# Breadboard_ProMini_v3.net
KiCad netlist of a schematic drawn in EAGLE
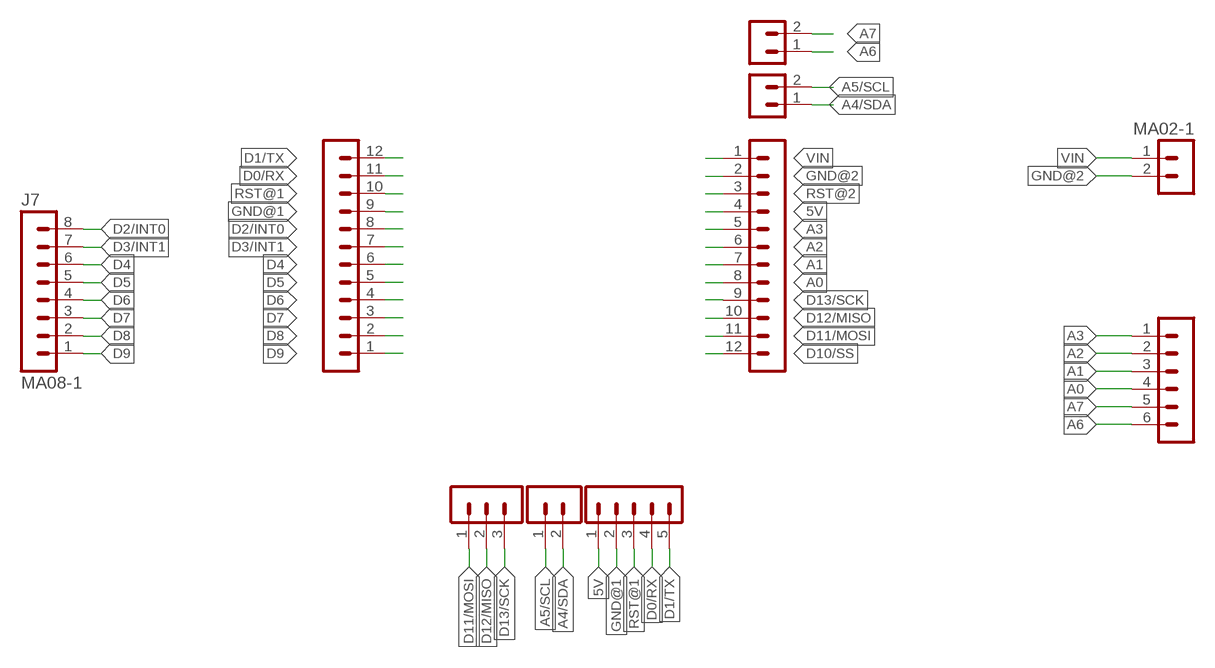
[diagram p0: schematic, sheet 1]

(export (version "E")
  (design (tool "Eeschema 10.0.6"))
  (components
    (comp (ref "J1")
      (value "MA05-1")
      (footprint "eagle-import:MA05-1")
      (libsource (lib "eagle-import") (part "MA05-1"))
    )
    (comp (ref "J3")
      (value "MA03-1")
      (footprint "eagle-import:MA03-1")
      (libsource (lib "eagle-import") (part "MA03-1"))
    )
    (comp (ref "J4")
      (value "MA12-1")
      (footprint "eagle-import:MA12-1")
      (libsource (lib "eagle-import") (part "MA12-1"))
    )
    (comp (ref "J5")
      (value "MA02-1")
      (footprint "eagle-import:MA02-1")
      (libsource (lib "eagle-import") (part "MA02-1"))
    )
    (comp (ref "J6")
      (value "MA02-1")
      (footprint "eagle-import:MA02-1")
      (libsource (lib "eagle-import") (part "00_marph_connectors_IDC_MA02-1"))
    )
    (comp (ref "J7")
      (value "MA08-1")
      (footprint "eagle-import:MA08-1")
      (libsource (lib "eagle-import") (part "MA08-1"))
    )
    (comp (ref "J8")
      (value "MA12-1")
      (footprint "eagle-import:MA12-1")
      (libsource (lib "eagle-import") (part "MA12-1"))
    )
    (comp (ref "J9")
      (value "MA02-1")
      (footprint "eagle-import:MA02-1")
      (libsource (lib "eagle-import") (part "00_marph_connectors_IDC_MA02-1"))
    )
    (comp (ref "J10")
      (value "MA02-1")
      (footprint "eagle-import:MA02-1")
      (libsource (lib "eagle-import") (part "MA02-1"))
    )
    (comp (ref "J11")
      (value "MA06-1")
      (footprint "eagle-import:MA06-1")
      (libsource (lib "eagle-import") (part "MA06-1"))
    )
  )
  (nets
    (net (code "1") (name "5V") (class "Default")
      (node (ref "J1") (pin "1") (pinfunction "1_1") (pintype "passive"))
      (node (ref "J8") (pin "4") (pinfunction "4_4") (pintype "passive"))
    )
    (net (code "2") (name "A0") (class "Default")
      (node (ref "J11") (pin "4") (pinfunction "4_4") (pintype "passive"))
      (node (ref "J8") (pin "8") (pinfunction "8_8") (pintype "passive"))
    )
    (net (code "3") (name "A1") (class "Default")
      (node (ref "J11") (pin "3") (pinfunction "3_3") (pintype "passive"))
      (node (ref "J8") (pin "7") (pinfunction "7_7") (pintype "passive"))
    )
    (net (code "4") (name "A2") (class "Default")
      (node (ref "J11") (pin "2") (pinfunction "2_2") (pintype "passive"))
      (node (ref "J8") (pin "6") (pinfunction "6_6") (pintype "passive"))
    )
    (net (code "5") (name "A3") (class "Default")
      (node (ref "J11") (pin "1") (pinfunction "1_1") (pintype "passive"))
      (node (ref "J8") (pin "5") (pinfunction "5_5") (pintype "passive"))
    )
    (net (code "6") (name "A4{slash}SDA") (class "Default")
      (node (ref "J10") (pin "1") (pinfunction "1_1") (pintype "passive"))
      (node (ref "J6") (pin "2") (pinfunction "2_2") (pintype "passive"))
    )
    (net (code "7") (name "A5{slash}SCL") (class "Default")
      (node (ref "J10") (pin "2") (pinfunction "2_2") (pintype "passive"))
      (node (ref "J6") (pin "1") (pinfunction "1_1") (pintype "passive"))
    )
    (net (code "8") (name "A6") (class "Default")
      (node (ref "J11") (pin "6") (pinfunction "6_6") (pintype "passive"))
      (node (ref "J5") (pin "1") (pinfunction "1_1") (pintype "passive"))
    )
    (net (code "9") (name "A7") (class "Default")
      (node (ref "J11") (pin "5") (pinfunction "5_5") (pintype "passive"))
      (node (ref "J5") (pin "2") (pinfunction "2_2") (pintype "passive"))
    )
    (net (code "10") (name "D0{slash}RX") (class "Default")
      (node (ref "J1") (pin "4") (pinfunction "4_4") (pintype "passive"))
      (node (ref "J4") (pin "11") (pinfunction "11_11") (pintype "passive"))
    )
    (net (code "11") (name "D1{slash}TX") (class "Default")
      (node (ref "J1") (pin "5") (pinfunction "5_5") (pintype "passive"))
      (node (ref "J4") (pin "12") (pinfunction "12_12") (pintype "passive"))
    )
    (net (code "12") (name "D2{slash}INT0") (class "Default")
      (node (ref "J4") (pin "8") (pinfunction "8_8") (pintype "passive"))
      (node (ref "J7") (pin "8") (pinfunction "8_8") (pintype "passive"))
    )
    (net (code "13") (name "D3{slash}INT1") (class "Default")
      (node (ref "J4") (pin "7") (pinfunction "7_7") (pintype "passive"))
      (node (ref "J7") (pin "7") (pinfunction "7_7") (pintype "passive"))
    )
    (net (code "14") (name "D4") (class "Default")
      (node (ref "J4") (pin "6") (pinfunction "6_6") (pintype "passive"))
      (node (ref "J7") (pin "6") (pinfunction "6_6") (pintype "passive"))
    )
    (net (code "15") (name "D5") (class "Default")
      (node (ref "J4") (pin "5") (pinfunction "5_5") (pintype "passive"))
      (node (ref "J7") (pin "5") (pinfunction "5_5") (pintype "passive"))
    )
    (net (code "16") (name "D6") (class "Default")
      (node (ref "J4") (pin "4") (pinfunction "4_4") (pintype "passive"))
      (node (ref "J7") (pin "4") (pinfunction "4_4") (pintype "passive"))
    )
    (net (code "17") (name "D7") (class "Default")
      (node (ref "J4") (pin "3") (pinfunction "3_3") (pintype "passive"))
      (node (ref "J7") (pin "3") (pinfunction "3_3") (pintype "passive"))
    )
    (net (code "18") (name "D8") (class "Default")
      (node (ref "J4") (pin "2") (pinfunction "2_2") (pintype "passive"))
      (node (ref "J7") (pin "2") (pinfunction "2_2") (pintype "passive"))
    )
    (net (code "19") (name "D9") (class "Default")
      (node (ref "J4") (pin "1") (pinfunction "1_1") (pintype "passive"))
      (node (ref "J7") (pin "1") (pinfunction "1_1") (pintype "passive"))
    )
    (net (code "20") (name "D10{slash}SS") (class "Default")
      (node (ref "J8") (pin "12") (pinfunction "12_12") (pintype "passive"))
    )
    (net (code "21") (name "D11{slash}MOSI") (class "Default")
      (node (ref "J3") (pin "1") (pinfunction "1_1") (pintype "passive"))
      (node (ref "J8") (pin "11") (pinfunction "11_11") (pintype "passive"))
    )
    (net (code "22") (name "D12{slash}MISO") (class "Default")
      (node (ref "J3") (pin "2") (pinfunction "2_2") (pintype "passive"))
      (node (ref "J8") (pin "10") (pinfunction "10_10") (pintype "passive"))
    )
    (net (code "23") (name "D13{slash}SCK") (class "Default")
      (node (ref "J3") (pin "3") (pinfunction "3_3") (pintype "passive"))
      (node (ref "J8") (pin "9") (pinfunction "9_9") (pintype "passive"))
    )
    (net (code "24") (name "GND@1") (class "Default")
      (node (ref "J1") (pin "2") (pinfunction "2_2") (pintype "passive"))
      (node (ref "J4") (pin "9") (pinfunction "9_9") (pintype "passive"))
    )
    (net (code "25") (name "GND@2") (class "Default")
      (node (ref "J8") (pin "2") (pinfunction "2_2") (pintype "passive"))
      (node (ref "J9") (pin "2") (pinfunction "2_2") (pintype "passive"))
    )
    (net (code "26") (name "RST@1") (class "Default")
      (node (ref "J1") (pin "3") (pinfunction "3_3") (pintype "passive"))
      (node (ref "J4") (pin "10") (pinfunction "10_10") (pintype "passive"))
    )
    (net (code "27") (name "RST@2") (class "Default")
      (node (ref "J8") (pin "3") (pinfunction "3_3") (pintype "passive"))
    )
    (net (code "28") (name "VIN") (class "Default")
      (node (ref "J8") (pin "1") (pinfunction "1_1") (pintype "passive"))
      (node (ref "J9") (pin "1") (pinfunction "1_1") (pintype "passive"))
    )
  )
)
